# SOIC-8-N_to_DIP-8.net
KiCad netlist of a schematic drawn in EAGLE
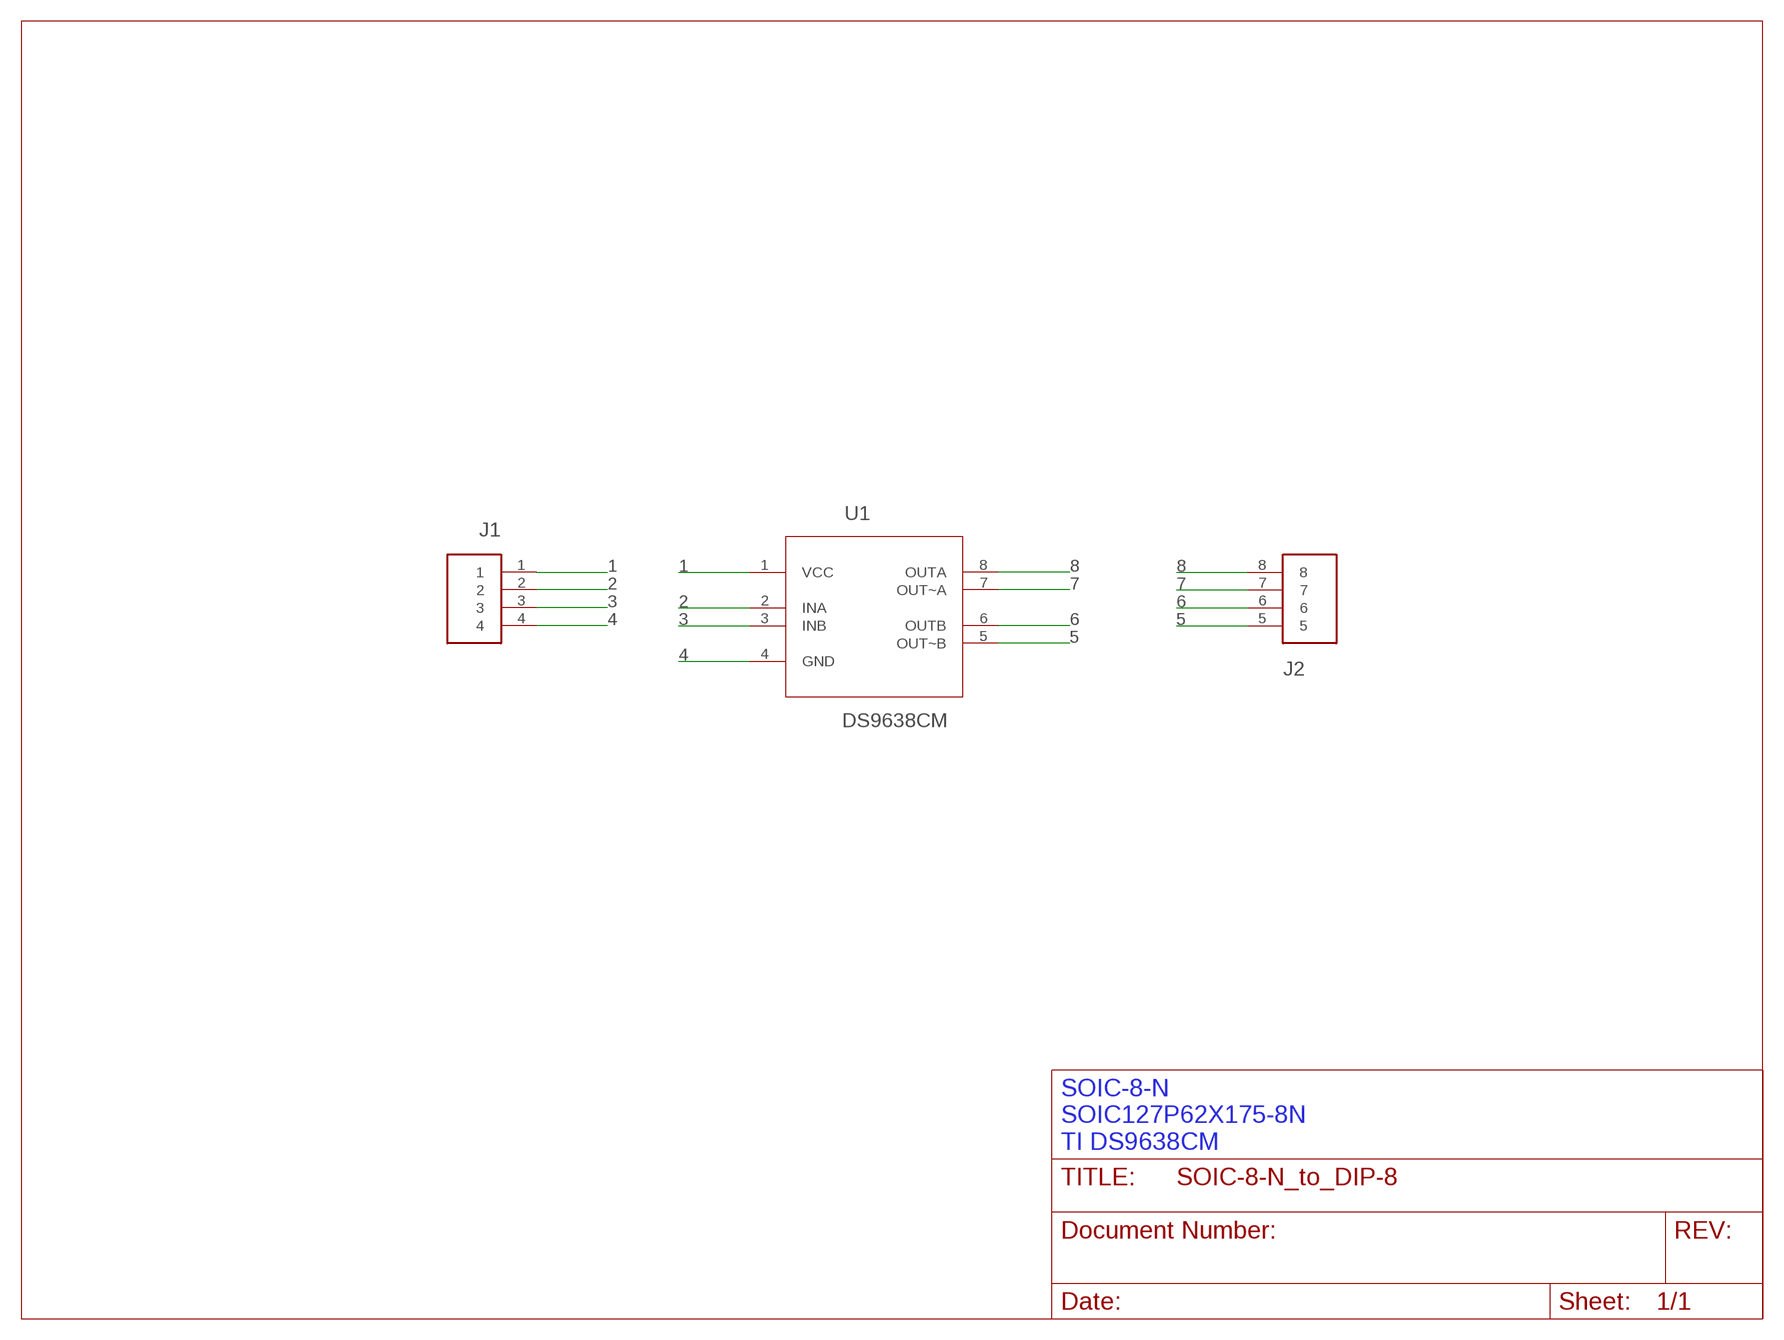
[diagram p0: schematic, sheet 1]

(export (version "E")
  (design (tool "Eeschema 10.0.6"))
  (components
    (comp (ref "J1")
      (value "CONNECTOR_4-0.100_VERTICAL")
      (footprint "eagle-import:68000-104HLF")
      (libsource (lib "eagle-import") (part "CONNECTOR_4-0.100_VERTICAL"))
    )
    (comp (ref "J2")
      (value "CONNECTOR_4_PINS_5-8")
      (footprint "eagle-import:68000-104HLF_PINS_5-8")
      (libsource (lib "eagle-import") (part "CONNECTOR_4_PINS_5-8"))
    )
    (comp (ref "U1")
      (value "DS9638CM")
      (footprint "eagle-import:SOIC127P62X175-8N")
      (fields (field (name "MF") "Texas Instruments") (field (name "MP") "DS9638CM/NOPB"))
      (libsource (lib "eagle-import") (part "DS9638CM"))
    )
  )
  (nets
    (net (code "1") (name "/1") (class "Default")
      (node (ref "J1") (pin "1") (pinfunction "1_1") (pintype "bidirectional"))
      (node (ref "U1") (pin "1") (pinfunction "VCC_1") (pintype "power_in"))
    )
    (net (code "2") (name "/2") (class "Default")
      (node (ref "J1") (pin "2") (pinfunction "2_2") (pintype "bidirectional"))
      (node (ref "U1") (pin "2") (pinfunction "INA_2") (pintype "input"))
    )
    (net (code "3") (name "/3") (class "Default")
      (node (ref "J1") (pin "3") (pinfunction "3_3") (pintype "bidirectional"))
      (node (ref "U1") (pin "3") (pinfunction "INB_3") (pintype "input"))
    )
    (net (code "4") (name "/4") (class "Default")
      (node (ref "J1") (pin "4") (pinfunction "4_4") (pintype "bidirectional"))
      (node (ref "U1") (pin "4") (pinfunction "GND_4") (pintype "passive"))
    )
    (net (code "5") (name "/5") (class "Default")
      (node (ref "J2") (pin "5") (pinfunction "5_5") (pintype "bidirectional"))
      (node (ref "U1") (pin "5") (pinfunction "OUT~{B}_5") (pintype "output"))
    )
    (net (code "6") (name "/6") (class "Default")
      (node (ref "J2") (pin "6") (pinfunction "6_6") (pintype "bidirectional"))
      (node (ref "U1") (pin "6") (pinfunction "OUTB_6") (pintype "output"))
    )
    (net (code "7") (name "/7") (class "Default")
      (node (ref "J2") (pin "7") (pinfunction "7_7") (pintype "bidirectional"))
      (node (ref "U1") (pin "7") (pinfunction "OUT~{A}_7") (pintype "output"))
    )
    (net (code "8") (name "/8") (class "Default")
      (node (ref "J2") (pin "8") (pinfunction "8_8") (pintype "bidirectional"))
      (node (ref "U1") (pin "8") (pinfunction "OUTA_8") (pintype "output"))
    )
  )
)
